# BatteryBoard.net
KiCad netlist of a schematic drawn in EAGLE
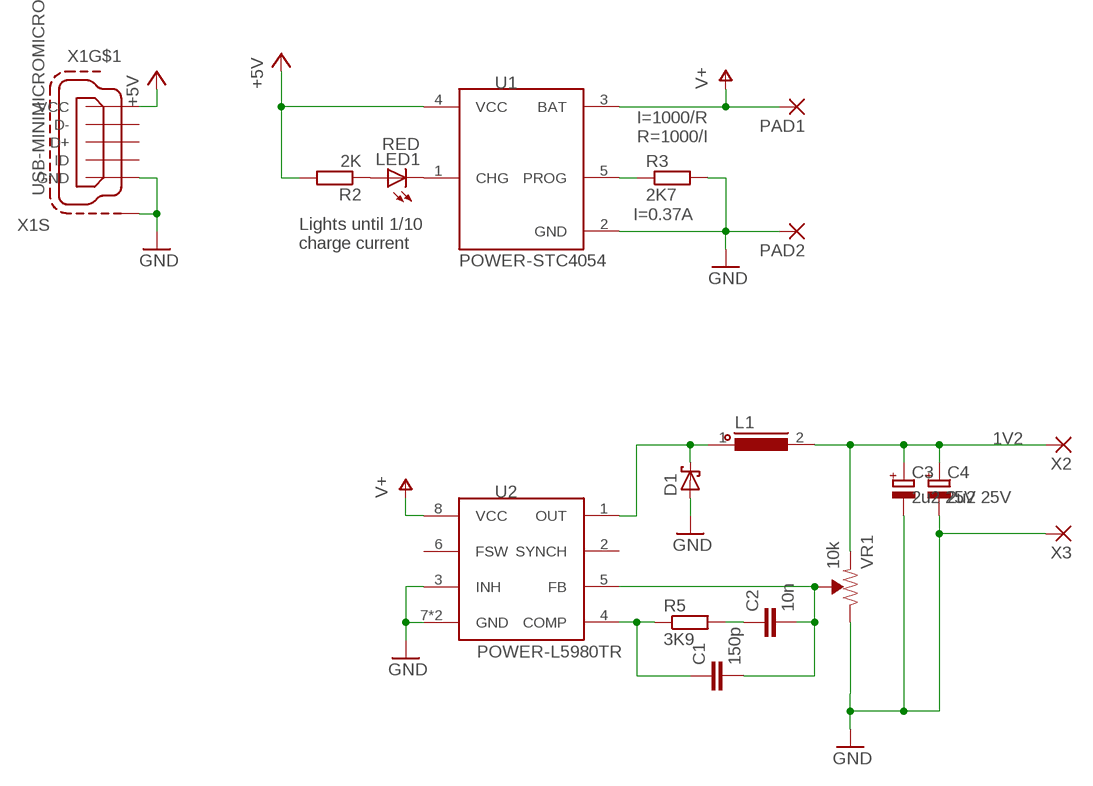
[diagram p0: schematic, sheet 1]

(export (version "E")
  (design (tool "Eeschema 10.0.6"))
  (components
    (comp (ref "C1")
      (value "150p")
      (footprint "eagle-import:CAP0805")
      (libsource (lib "eagle-import") (part "CAP_0805"))
    )
    (comp (ref "C2")
      (value "10n")
      (footprint "eagle-import:CAP0805")
      (libsource (lib "eagle-import") (part "CAP_0805"))
    )
    (comp (ref "C3")
      (value "2u2 25V")
      (footprint "eagle-import:CAPMP3317X180")
      (libsource (lib "eagle-import") (part "CAP-POL_CAPE3216-A"))
    )
    (comp (ref "C4")
      (value "2u2 25V")
      (footprint "eagle-import:CAPMP3317X180")
      (libsource (lib "eagle-import") (part "CAP-POL_CAPE3216-A"))
    )
    (comp (ref "D1")
      (value "DIODE-SH_SMA")
      (footprint "eagle-import:DO214AC")
      (libsource (lib "eagle-import") (part "DIODE-SH_SMA"))
    )
    (comp (ref "L1")
      (value "INDUCTORNL4532")
      (footprint "eagle-import:INDM4232X320")
      (libsource (lib "eagle-import") (part "INDUCTORNL4532"))
    )
    (comp (ref "LED1")
      (value "RED")
      (footprint "eagle-import:LED1206")
      (libsource (lib "eagle-import") (part "LED_1206"))
    )
    (comp (ref "PAD1")
      (value "WIREPAD-SMD2")
      (footprint "eagle-import:PAD-1.27X2.54")
      (libsource (lib "eagle-import") (part "WIREPAD-SMD2"))
    )
    (comp (ref "PAD2")
      (value "WIREPAD-SMD2")
      (footprint "eagle-import:PAD-1.27X2.54")
      (libsource (lib "eagle-import") (part "WIREPAD-SMD2"))
    )
    (comp (ref "R2")
      (value "2K")
      (footprint "eagle-import:RESC2012X50")
      (libsource (lib "eagle-import") (part "R_R0805"))
    )
    (comp (ref "R3")
      (value "2K7")
      (footprint "eagle-import:RESC2012X50")
      (libsource (lib "eagle-import") (part "R_R0805"))
    )
    (comp (ref "R5")
      (value "3K9")
      (footprint "eagle-import:RESC2012X50")
      (libsource (lib "eagle-import") (part "R_R0805"))
    )
    (comp (ref "U1")
      (value "POWER-STC4054")
      (footprint "eagle-import:SOT95P280X145-5")
      (libsource (lib "eagle-import") (part "POWER-STC4054"))
    )
    (comp (ref "U2")
      (value "POWER-L5980TR")
      (footprint "eagle-import:QFPN8")
      (libsource (lib "eagle-import") (part "POWER-L5980TR"))
    )
    (comp (ref "VR1")
      (value "10k")
      (footprint "eagle-import:TRIMPOT-SMD-TC33X")
      (libsource (lib "eagle-import") (part "TRIMPOT-SMD-3MM-OPEN-1/10W-25%"))
    )
    (comp (ref "X1")
      (value "USB-MINIMICROMICRO")
      (footprint "eagle-import:USB-B-MICRO-SMD")
      (libsource (lib "eagle-import") (part "USB-MINIMICROMICRO"))
    )
    (comp (ref "X2")
      (value "WIREPAD-SMD2")
      (footprint "eagle-import:PAD-1.27X2.54")
      (libsource (lib "eagle-import") (part "WIREPAD-SMD2"))
    )
    (comp (ref "X3")
      (value "WIREPAD-SMD2")
      (footprint "eagle-import:PAD-1.27X2.54")
      (libsource (lib "eagle-import") (part "WIREPAD-SMD2"))
    )
  )
  (nets
    (net (code "1") (name "+5V") (class "Default")
      (node (ref "R2") (pin "2") (pinfunction "2_2") (pintype "passive"))
      (node (ref "U1") (pin "4") (pinfunction "VCC_4") (pintype "power_in"))
      (node (ref "X1") (pin "VBUS") (pinfunction "VCC_VBUS") (pintype "passive"))
    )
    (net (code "2") (name "/1V2") (class "Default")
      (node (ref "C3") (pin "1") (pinfunction "+_1") (pintype "passive"))
      (node (ref "C4") (pin "1") (pinfunction "+_1") (pintype "passive"))
      (node (ref "L1") (pin "2") (pinfunction "2_2") (pintype "passive"))
      (node (ref "VR1") (pin "3") (pinfunction "CCW_3") (pintype "passive"))
      (node (ref "X2") (pin "P$1") (pinfunction "P_P$1") (pintype "passive"))
    )
    (net (code "3") (name "GND") (class "Default")
      (node (ref "C3") (pin "2") (pinfunction "-_2") (pintype "passive"))
      (node (ref "C4") (pin "2") (pinfunction "-_2") (pintype "passive"))
      (node (ref "D1") (pin "A") (pinfunction "A_A") (pintype "passive"))
      (node (ref "PAD2") (pin "P$1") (pinfunction "P_P$1") (pintype "passive"))
      (node (ref "R3") (pin "2") (pinfunction "2_2") (pintype "passive"))
      (node (ref "U1") (pin "2") (pinfunction "GND_2") (pintype "power_in"))
      (node (ref "U2") (pin "3") (pinfunction "INH_3") (pintype "bidirectional"))
      (node (ref "U2") (pin "7") (pinfunction "GND_7") (pintype "bidirectional"))
      (node (ref "U2") (pin "EXP") (pinfunction "GND_EXP") (pintype "bidirectional"))
      (node (ref "VR1") (pin "1") (pinfunction "CW_1") (pintype "passive"))
      (node (ref "X1") (pin "GND") (pinfunction "GND_GND") (pintype "passive"))
      (node (ref "X1") (pin "SHIELD1") (pinfunction "S1_SHIELD1") (pintype "passive"))
      (node (ref "X1") (pin "SHIELD2") (pinfunction "S1_SHIELD2") (pintype "passive"))
      (node (ref "X1") (pin "SHIELD3") (pinfunction "S1_SHIELD3") (pintype "passive"))
      (node (ref "X3") (pin "P$1") (pinfunction "P_P$1") (pintype "passive"))
    )
    (net (code "4") (name "Net-(C2-Pad1)") (class "Default")
      (node (ref "C2") (pin "1") (pinfunction "1_1") (pintype "passive"))
      (node (ref "R5") (pin "2") (pinfunction "2_2") (pintype "passive"))
    )
    (net (code "5") (name "Net-(LED1-PadA)") (class "Default")
      (node (ref "LED1") (pin "A") (pinfunction "A_A") (pintype "passive"))
      (node (ref "R2") (pin "1") (pinfunction "1_1") (pintype "passive"))
    )
    (net (code "6") (name "Net-(U1-CHG)") (class "Default")
      (node (ref "LED1") (pin "C") (pinfunction "C_C") (pintype "passive"))
      (node (ref "U1") (pin "1") (pinfunction "CHG_1") (pintype "output"))
    )
    (net (code "7") (name "Net-(U1-PROG)") (class "Default")
      (node (ref "R3") (pin "1") (pinfunction "1_1") (pintype "passive"))
      (node (ref "U1") (pin "5") (pinfunction "PROG_5") (pintype "bidirectional"))
    )
    (net (code "8") (name "Net-(U2-COMP)") (class "Default")
      (node (ref "C1") (pin "1") (pinfunction "1_1") (pintype "passive"))
      (node (ref "R5") (pin "1") (pinfunction "1_1") (pintype "passive"))
      (node (ref "U2") (pin "4") (pinfunction "COMP_4") (pintype "bidirectional"))
    )
    (net (code "9") (name "Net-(U2-FB)") (class "Default")
      (node (ref "C1") (pin "2") (pinfunction "2_2") (pintype "passive"))
      (node (ref "C2") (pin "2") (pinfunction "2_2") (pintype "passive"))
      (node (ref "U2") (pin "5") (pinfunction "FB_5") (pintype "bidirectional"))
      (node (ref "VR1") (pin "2") (pinfunction "WIPER_2") (pintype "passive"))
    )
    (net (code "10") (name "Net-(U2-OUT)") (class "Default")
      (node (ref "D1") (pin "C") (pinfunction "C_C") (pintype "passive"))
      (node (ref "L1") (pin "1") (pinfunction "1_1") (pintype "passive"))
      (node (ref "U2") (pin "1") (pinfunction "OUT_1") (pintype "bidirectional"))
    )
    (net (code "11") (name "V+") (class "Default")
      (node (ref "PAD1") (pin "P$1") (pinfunction "P_P$1") (pintype "passive"))
      (node (ref "U1") (pin "3") (pinfunction "BAT_3") (pintype "bidirectional"))
      (node (ref "U2") (pin "8") (pinfunction "VCC_8") (pintype "bidirectional"))
    )
    (net (code "12") (name "unconnected-(U2-FSW-Pad6)") (class "Default")
      (node (ref "U2") (pin "6") (pinfunction "FSW_6") (pintype "bidirectional"))
    )
    (net (code "13") (name "unconnected-(U2-SYNCH-Pad2)") (class "Default")
      (node (ref "U2") (pin "2") (pinfunction "SYNCH_2") (pintype "bidirectional"))
    )
    (net (code "14") (name "unconnected-(X1-PadD+)") (class "Default")
      (node (ref "X1") (pin "D+") (pinfunction "D+_D+") (pintype "passive"))
    )
    (net (code "15") (name "unconnected-(X1-PadD-)") (class "Default")
      (node (ref "X1") (pin "D-") (pinfunction "D-_D-") (pintype "passive"))
    )
    (net (code "16") (name "unconnected-(X1-PadID)") (class "Default")
      (node (ref "X1") (pin "ID") (pinfunction "ID_ID") (pintype "passive"))
    )
  )
)
